# LED_V3_0.net
KiCad netlist of a schematic drawn in EasyEDA Pro
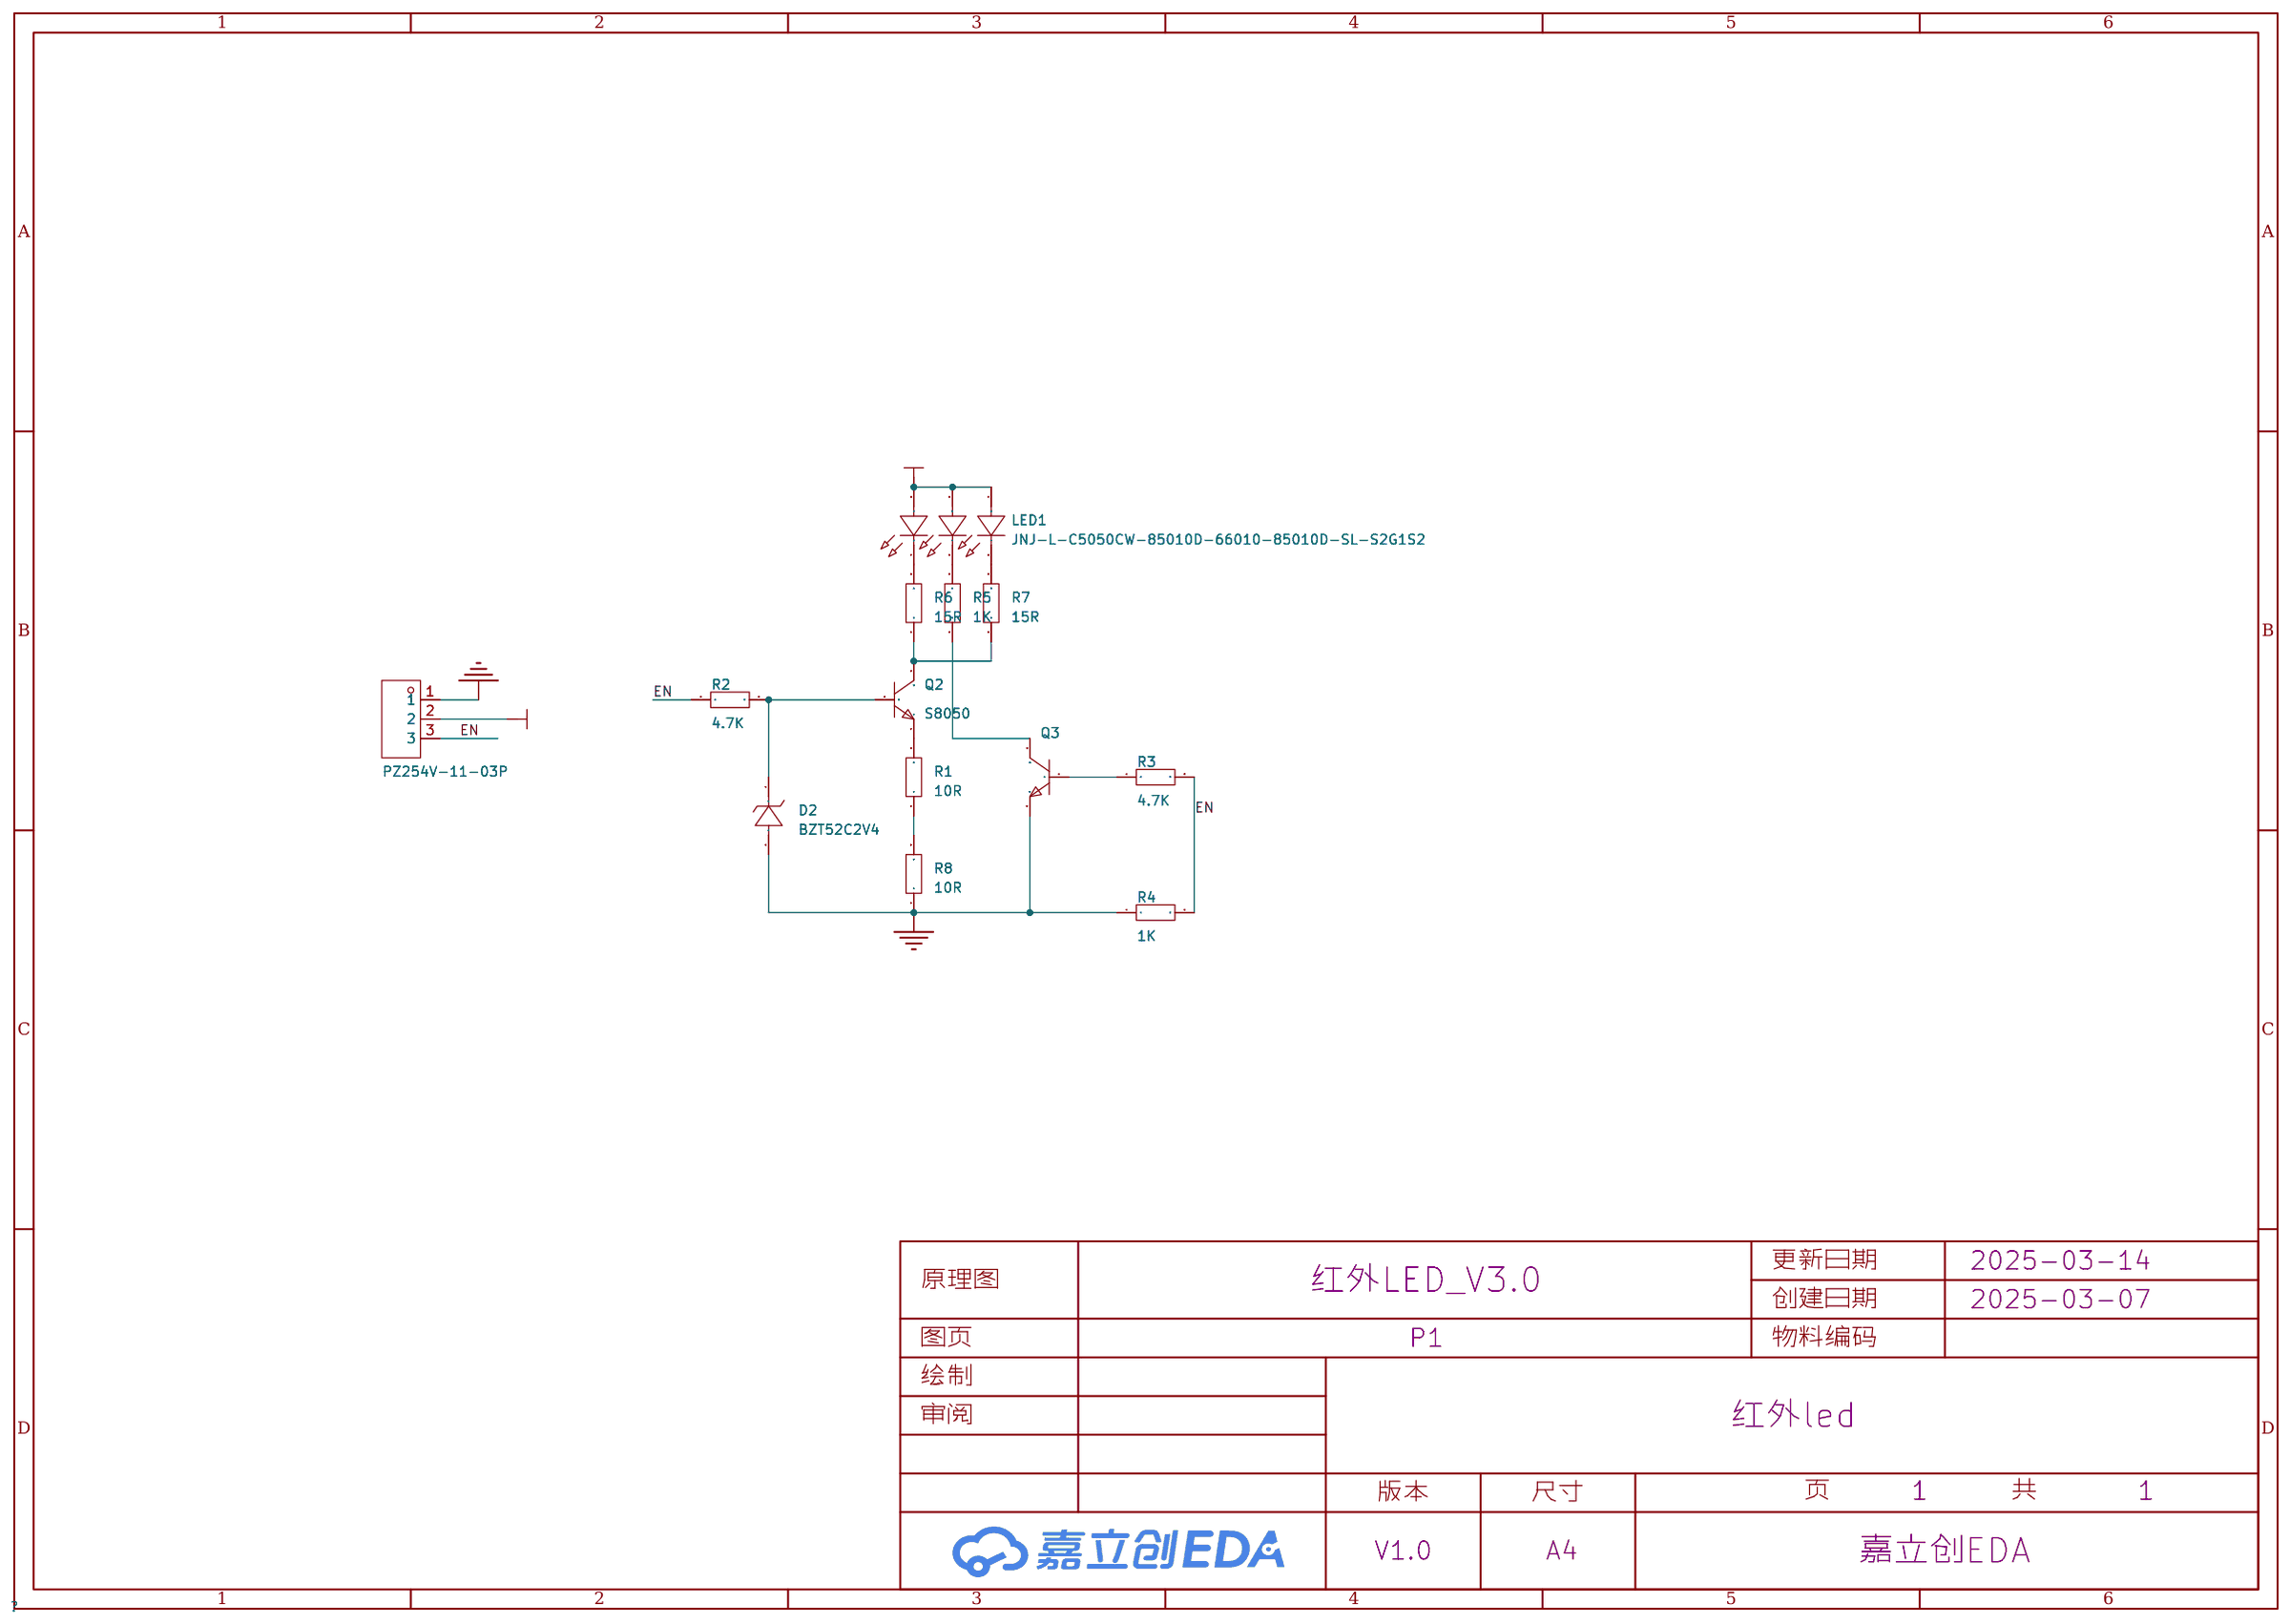
[diagram p0: schematic sheet]

(export (version "E")
  (design (tool "Eeschema 10.0.6"))
  (components
    (comp (ref "D2")
      (value "BZT52C2V4")
      (footprint "easyedapro:SOD-123_L2.7-W1.6-LS3.7-RD")
      (description "二极管配置:独立式;稳压值(标称值):2.4V;稳压值(范围):2.2V~2.6V;耗散功率(Pd):350mW;")
      (fields (field (name "Manufacturer") "宏嘉诚"))
      (libsource (lib "easyedapro") (part "BZT52C2V4_C22375296"))
    )
    (comp (ref "H1")
      (value "PZ254V-11-03P")
      (footprint "easyedapro:HDR-TH_3P-P2.54-V-M")
      (fields (field (name "Manufacturer") "XFCN(兴飞)"))
      (libsource (lib "easyedapro") (part "PZ254V-11-03P_C2937625"))
    )
    (comp (ref "LED1")
      (value "JNJ-L-C5050CW-85010D-66010-85010D-SL-S2G1S2")
      (footprint "easyedapro:LED-SMD_6P-L5.0-W5.0-P1.50-LS5.4-BL-1")
      (fields (field (name "Manufacturer") "JNJ OPTOELECTRONICS(强生光电)"))
      (libsource (lib "easyedapro") (part "JNJ-L-C5050CW-85010D-66010-85010D-SL-S2G1S2"))
    )
    (comp (ref "Q2")
      (value "S8050")
      (footprint "easyedapro:SOT-23-3_L2.9-W1.3-P1.90-LS2.3-BR")
      (description "晶体管类型:NPN;集电极电流(Ic):500mA;集射极击穿电压(Vceo):25V;功率(Pd):300mW;直流电流增益(hFE@Ic,Vce):120@50mA,1.0V;")
      (fields (field (name "Manufacturer") "宏迦橙"))
      (libsource (lib "easyedapro") (part "S8050_C20069125"))
    )
    (comp (ref "Q3")
      (value "~")
      (footprint "easyedapro:S8050_SOT-23")
      (libsource (lib "easyedapro") (part "NPN"))
    )
    (comp (ref "R1") (value "10R") (footprint "easyedapro:R0603") (libsource (lib "easyedapro") (part "电阻")))
    (comp (ref "R2") (value "4.7K") (footprint "easyedapro:R0603") (libsource (lib "easyedapro") (part "电阻")))
    (comp (ref "R3") (value "4.7K") (footprint "easyedapro:R0603") (libsource (lib "easyedapro") (part "电阻")))
    (comp (ref "R4") (value "1K") (footprint "easyedapro:R0603") (libsource (lib "easyedapro") (part "电阻")))
    (comp (ref "R5") (value "1K") (footprint "easyedapro:R0603") (libsource (lib "easyedapro") (part "电阻")))
    (comp (ref "R6") (value "15R") (footprint "easyedapro:R0603") (libsource (lib "easyedapro") (part "电阻")))
    (comp (ref "R7") (value "15R") (footprint "easyedapro:R0603") (libsource (lib "easyedapro") (part "电阻")))
    (comp (ref "R8") (value "10R") (footprint "easyedapro:R0603") (libsource (lib "easyedapro") (part "电阻")))
  )
  (nets
    (net (code "1") (name "/EN") (class "Default")
      (node (ref "H1") (pin "3") (pinfunction "3_3") (pintype "unspecified"))
      (node (ref "R2") (pin "1") (pinfunction "1_1") (pintype "input"))
      (node (ref "R3") (pin "2") (pinfunction "2_2") (pintype "input"))
      (node (ref "R4") (pin "2") (pinfunction "2_2") (pintype "input"))
    )
    (net (code "2") (name "5V") (class "Default")
      (node (ref "H1") (pin "2") (pinfunction "2_2") (pintype "unspecified"))
      (node (ref "LED1") (pin "4") (pinfunction "A_4") (pintype "unspecified"))
      (node (ref "LED1") (pin "5") (pinfunction "A_5") (pintype "unspecified"))
      (node (ref "LED1") (pin "6") (pinfunction "A_6") (pintype "unspecified"))
    )
    (net (code "3") (name "GND") (class "Default")
      (node (ref "D2") (pin "2") (pinfunction "A_2") (pintype "unspecified"))
      (node (ref "H1") (pin "1") (pinfunction "1_1") (pintype "unspecified"))
      (node (ref "Q3") (pin "2") (pinfunction "2_2") (pintype "unspecified"))
      (node (ref "R4") (pin "1") (pinfunction "1_1") (pintype "input"))
      (node (ref "R8") (pin "1") (pinfunction "1_1") (pintype "input"))
    )
    (net (code "4") (name "Net-(D2-K)") (class "Default")
      (node (ref "D2") (pin "1") (pinfunction "K_1") (pintype "unspecified"))
      (node (ref "Q2") (pin "1") (pinfunction "B_1") (pintype "input"))
      (node (ref "R2") (pin "2") (pinfunction "2_2") (pintype "input"))
    )
    (net (code "5") (name "Net-(LED1-K-Pad1)") (class "Default")
      (node (ref "LED1") (pin "1") (pinfunction "K_1") (pintype "unspecified"))
      (node (ref "R6") (pin "2") (pinfunction "2_2") (pintype "input"))
    )
    (net (code "6") (name "Net-(LED1-K-Pad2)") (class "Default")
      (node (ref "LED1") (pin "2") (pinfunction "K_2") (pintype "unspecified"))
      (node (ref "R5") (pin "2") (pinfunction "2_2") (pintype "input"))
    )
    (net (code "7") (name "Net-(LED1-K-Pad3)") (class "Default")
      (node (ref "LED1") (pin "3") (pinfunction "K_3") (pintype "unspecified"))
      (node (ref "R7") (pin "2") (pinfunction "2_2") (pintype "input"))
    )
    (net (code "8") (name "Net-(Q2-C)") (class "Default")
      (node (ref "Q2") (pin "3") (pinfunction "C_3") (pintype "input"))
      (node (ref "R6") (pin "1") (pinfunction "1_1") (pintype "input"))
      (node (ref "R7") (pin "1") (pinfunction "1_1") (pintype "input"))
    )
    (net (code "9") (name "Net-(Q2-E)") (class "Default")
      (node (ref "Q2") (pin "2") (pinfunction "E_2") (pintype "input"))
      (node (ref "R1") (pin "2") (pinfunction "2_2") (pintype "input"))
    )
    (net (code "10") (name "Net-(Q3-Pad1)") (class "Default")
      (node (ref "Q3") (pin "1") (pinfunction "1_1") (pintype "unspecified"))
      (node (ref "R3") (pin "1") (pinfunction "1_1") (pintype "input"))
    )
    (net (code "11") (name "Net-(Q3-Pad3)") (class "Default")
      (node (ref "Q3") (pin "3") (pinfunction "3_3") (pintype "unspecified"))
      (node (ref "R5") (pin "1") (pinfunction "1_1") (pintype "input"))
    )
    (net (code "12") (name "Net-(R1-Pad1)") (class "Default")
      (node (ref "R1") (pin "1") (pinfunction "1_1") (pintype "input"))
      (node (ref "R8") (pin "2") (pinfunction "2_2") (pintype "input"))
    )
  )
)
